# SolarP.net
KiCad netlist of a schematic drawn in Altium Designer
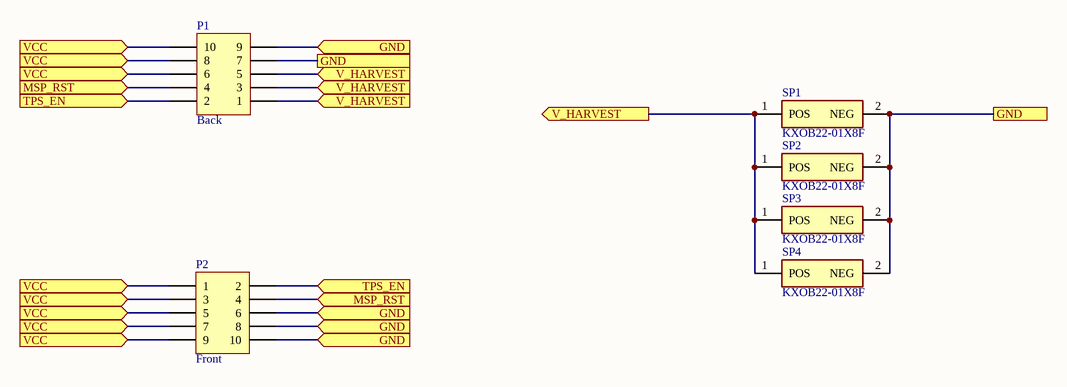
[diagram p0: SolarP.SchDoc]

(export (version "E")
  (design (tool "Eeschema 10.0.6"))
  (components
    (comp (ref "P1")
      (value "Back")
      (footprint "CLE-105-01-X-DV")
      (description "Back board connector")
      (fields (field (name "PUBLISHER") "Altium Limited"))
      (libsource (lib "") (part "Header 5X2_1"))
    )
    (comp (ref "P2")
      (value "Front")
      (footprint "CLE-105-01-X-DV")
      (description "Front board connector")
      (fields (field (name "PUBLISHER") "Altium Limited"))
      (libsource (lib "Miscellaneous Connectors") (part "Header 5X2"))
    )
    (comp (ref "SP1")
      (value "KXOB22-01X8F")
      (footprint "KXOB22-12X1F")
      (description "Monocrystalline Solar Cell 22% 2-Pin SMD")
      (fields (field (name "MANUFACTURER_PART_NUMBER") "KXOB22-12X1F"))
      (libsource (lib "SamacSys") (part "KXOB22-12X1F"))
    )
    (comp (ref "SP2")
      (value "KXOB22-01X8F")
      (footprint "KXOB22-12X1F")
      (description "Monocrystalline Solar Cell 22% 2-Pin SMD")
      (fields (field (name "MANUFACTURER_PART_NUMBER") "KXOB22-12X1F"))
      (libsource (lib "SamacSys") (part "KXOB22-12X1F"))
    )
    (comp (ref "SP3")
      (value "KXOB22-01X8F")
      (footprint "KXOB22-12X1F")
      (description "Monocrystalline Solar Cell 22% 2-Pin SMD")
      (fields (field (name "MANUFACTURER_PART_NUMBER") "KXOB22-12X1F"))
      (libsource (lib "SamacSys") (part "KXOB22-12X1F"))
    )
    (comp (ref "SP4")
      (value "KXOB22-01X8F")
      (footprint "KXOB22-12X1F")
      (description "Monocrystalline Solar Cell 22% 2-Pin SMD")
      (fields (field (name "MANUFACTURER_PART_NUMBER") "KXOB22-12X1F"))
      (libsource (lib "SamacSys") (part "KXOB22-12X1F"))
    )
  )
  (nets
    (net (code "1") (name "/GND") (class "Default")
      (node (ref "P1") (pin "7") (pinfunction "7_7") (pintype "passive"))
      (node (ref "P1") (pin "9") (pinfunction "9_9") (pintype "passive"))
      (node (ref "P2") (pin "10") (pinfunction "10_10") (pintype "passive"))
      (node (ref "P2") (pin "6") (pinfunction "6_6") (pintype "passive"))
      (node (ref "P2") (pin "8") (pinfunction "8_8") (pintype "passive"))
      (node (ref "SP1") (pin "2") (pinfunction "NEG_2") (pintype "power_in"))
      (node (ref "SP2") (pin "2") (pinfunction "NEG_2") (pintype "power_in"))
      (node (ref "SP3") (pin "2") (pinfunction "NEG_2") (pintype "power_in"))
      (node (ref "SP4") (pin "2") (pinfunction "NEG_2") (pintype "power_in"))
    )
    (net (code "2") (name "/MSP_RST") (class "Default")
      (node (ref "P1") (pin "4") (pinfunction "4_4") (pintype "passive"))
      (node (ref "P2") (pin "4") (pinfunction "4_4") (pintype "passive"))
    )
    (net (code "3") (name "/TPS_EN") (class "Default")
      (node (ref "P1") (pin "2") (pinfunction "2_2") (pintype "passive"))
      (node (ref "P2") (pin "2") (pinfunction "2_2") (pintype "passive"))
    )
    (net (code "4") (name "/VCC") (class "Default")
      (node (ref "P1") (pin "10") (pinfunction "10_10") (pintype "passive"))
      (node (ref "P1") (pin "6") (pinfunction "6_6") (pintype "passive"))
      (node (ref "P1") (pin "8") (pinfunction "8_8") (pintype "passive"))
      (node (ref "P2") (pin "1") (pinfunction "1_1") (pintype "passive"))
      (node (ref "P2") (pin "3") (pinfunction "3_3") (pintype "passive"))
      (node (ref "P2") (pin "5") (pinfunction "5_5") (pintype "passive"))
      (node (ref "P2") (pin "7") (pinfunction "7_7") (pintype "passive"))
      (node (ref "P2") (pin "9") (pinfunction "9_9") (pintype "passive"))
    )
    (net (code "5") (name "/V_HARVEST") (class "Default")
      (node (ref "P1") (pin "1") (pinfunction "1_1") (pintype "passive"))
      (node (ref "P1") (pin "3") (pinfunction "3_3") (pintype "passive"))
      (node (ref "P1") (pin "5") (pinfunction "5_5") (pintype "passive"))
      (node (ref "SP1") (pin "1") (pinfunction "POS_1") (pintype "power_in"))
      (node (ref "SP2") (pin "1") (pinfunction "POS_1") (pintype "power_in"))
      (node (ref "SP3") (pin "1") (pinfunction "POS_1") (pintype "power_in"))
      (node (ref "SP4") (pin "1") (pinfunction "POS_1") (pintype "power_in"))
    )
  )
)
